# ESPRO_2.net
KiCad netlist of a schematic drawn in EAGLE
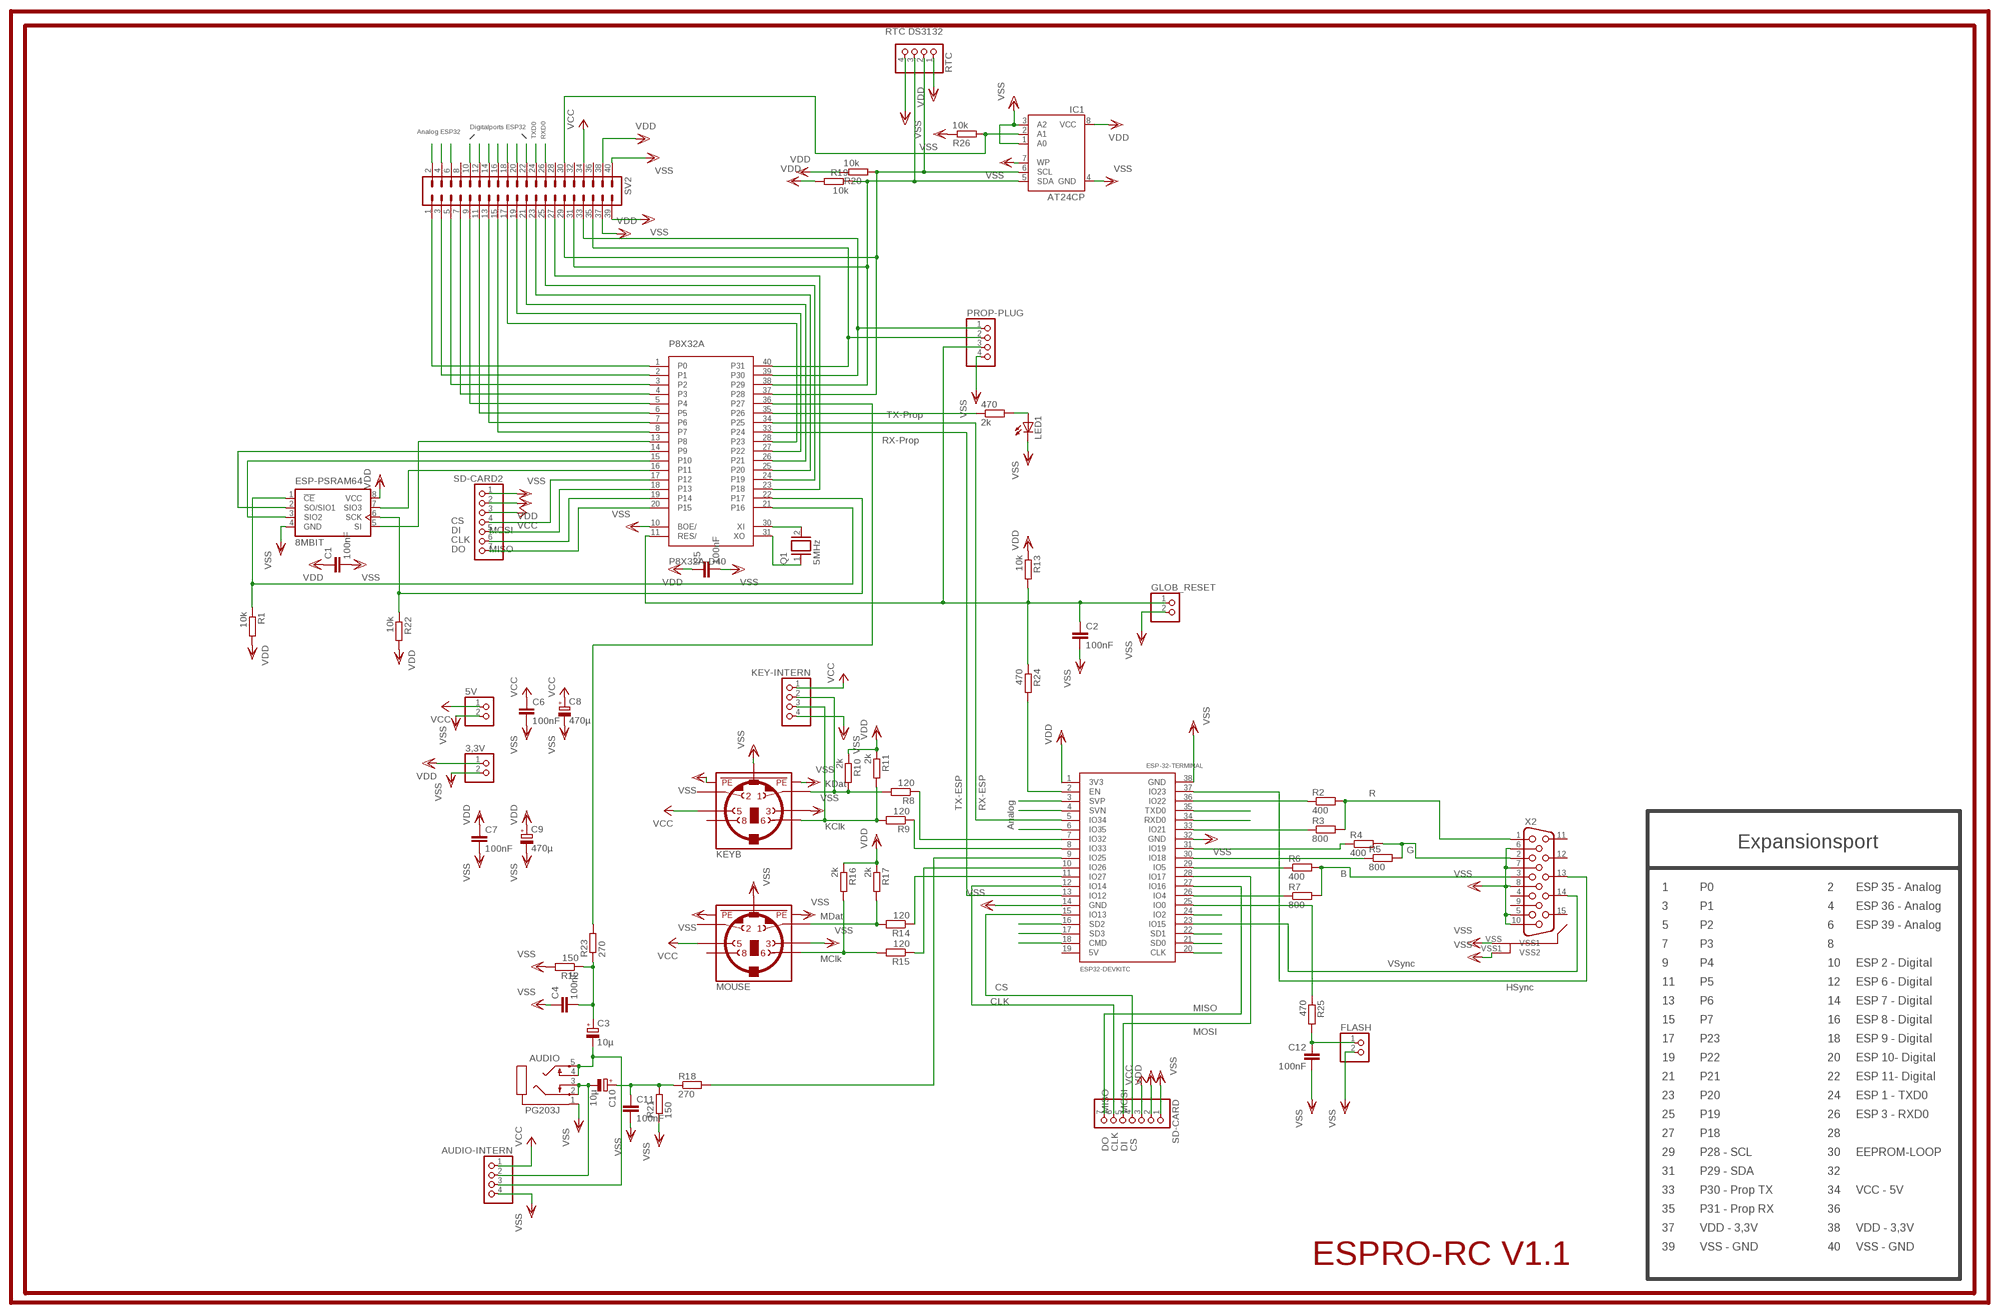
[diagram p0: schematic, sheet 1]

(export (version "E")
  (design (tool "Eeschema 10.0.6"))
  (components
    (comp (ref "3,3V")
      (value "PINHD-1X2")
      (footprint "eagle-import:1X02")
      (libsource (lib "eagle-import") (part "PINHD-1X2"))
    )
    (comp (ref "5V")
      (value "PINHD-1X2")
      (footprint "eagle-import:1X02")
      (libsource (lib "eagle-import") (part "PINHD-1X2"))
    )
    (comp (ref "470")
      (value "2k")
      (footprint "eagle-import:0204_7")
      (libsource (lib "eagle-import") (part "R-EU_0204/7"))
    )
    (comp (ref "AUDIO")
      (value "PG203J")
      (footprint "eagle-import:PG203J")
      (libsource (lib "eagle-import") (part "PG203J"))
    )
    (comp (ref "AUDIO-INTERN")
      (value "PINHD-1X4")
      (footprint "eagle-import:1X04")
      (libsource (lib "eagle-import") (part "PINHD-1X4"))
    )
    (comp (ref "C1")
      (value "100nF")
      (footprint "eagle-import:C025-030X050")
      (libsource (lib "eagle-import") (part "C-EU025-030X050"))
    )
    (comp (ref "C2")
      (value "100nF")
      (footprint "eagle-import:C025-030X050")
      (libsource (lib "eagle-import") (part "C-EU025-030X050"))
    )
    (comp (ref "C3")
      (value "10µ")
      (footprint "eagle-import:E2-4")
      (libsource (lib "eagle-import") (part "CPOL-EUE2-4"))
    )
    (comp (ref "C4")
      (value "100nF")
      (footprint "eagle-import:C025-030X050")
      (libsource (lib "eagle-import") (part "C-EU025-030X050"))
    )
    (comp (ref "C5")
      (value "100nF")
      (footprint "eagle-import:C025-030X050")
      (libsource (lib "eagle-import") (part "C-EU025-030X050"))
    )
    (comp (ref "C6")
      (value "100nF")
      (footprint "eagle-import:C025-030X050")
      (libsource (lib "eagle-import") (part "C-EU025-030X050"))
    )
    (comp (ref "C7")
      (value "100nF")
      (footprint "eagle-import:C025-030X050")
      (libsource (lib "eagle-import") (part "C-EU025-030X050"))
    )
    (comp (ref "C8")
      (value "470µ")
      (footprint "eagle-import:E3,5-10")
      (libsource (lib "eagle-import") (part "CPOL-EUE3.5-10"))
    )
    (comp (ref "C9")
      (value "470µ")
      (footprint "eagle-import:E3,5-10")
      (libsource (lib "eagle-import") (part "CPOL-EUE3.5-10"))
    )
    (comp (ref "C10")
      (value "10µ")
      (footprint "eagle-import:E2-4")
      (libsource (lib "eagle-import") (part "CPOL-EUE2-4"))
    )
    (comp (ref "C11")
      (value "100nF")
      (footprint "eagle-import:C025-030X050")
      (libsource (lib "eagle-import") (part "C-EU025-030X050"))
    )
    (comp (ref "C12")
      (value "100nF")
      (footprint "eagle-import:C025-030X050")
      (libsource (lib "eagle-import") (part "C-EU025-030X050"))
    )
    (comp (ref "ESP-32-TERMINAL")
      (value "ESP32DEVKITC")
      (footprint "eagle-import:ESP32-DEVKITC")
      (libsource (lib "eagle-import") (part "ESP32DEVKITC"))
    )
    (comp (ref "ESP-PSRAM64")
      (value "8MBIT")
      (footprint "eagle-import:DIL08")
      (libsource (lib "eagle-import") (part "AT25P"))
    )
    (comp (ref "FLASH")
      (value "PINHD-1X2")
      (footprint "eagle-import:1X02")
      (libsource (lib "eagle-import") (part "PINHD-1X2"))
    )
    (comp (ref "GLOB_RESET")
      (value "PINHD-1X2")
      (footprint "eagle-import:1X02")
      (libsource (lib "eagle-import") (part "PINHD-1X2"))
    )
    (comp (ref "IC1")
      (value "AT24CP")
      (footprint "eagle-import:DIL08")
      (fields (field (name "MPN") "AT24C1024BW-SH-B"))
      (libsource (lib "eagle-import") (part "AT24CP"))
    )
    (comp (ref "KEY-INTERN")
      (value "PINHD-1X4")
      (footprint "eagle-import:1X04")
      (libsource (lib "eagle-import") (part "PINHD-1X4"))
    )
    (comp (ref "KEYB")
      (value "MINI_DIN_6")
      (footprint "eagle-import:M_DIN6")
      (libsource (lib "eagle-import") (part "MINI_DIN_6"))
    )
    (comp (ref "LED1")
      (value "LED5MM")
      (footprint "eagle-import:LED5MM")
      (libsource (lib "eagle-import") (part "LED5MM"))
    )
    (comp (ref "MOUSE")
      (value "MINI_DIN_6")
      (footprint "eagle-import:M_DIN6")
      (libsource (lib "eagle-import") (part "MINI_DIN_6"))
    )
    (comp (ref "P8X32A")
      (value "P8X32A-D40")
      (footprint "eagle-import:P8X32A-D40")
      (libsource (lib "eagle-import") (part "P8X32A-D40"))
    )
    (comp (ref "PROP-PLUG")
      (value "PINHD-1X4")
      (footprint "eagle-import:1X04")
      (libsource (lib "eagle-import") (part "PINHD-1X4"))
    )
    (comp (ref "Q1")
      (value "5MHz")
      (footprint "eagle-import:QS")
      (libsource (lib "eagle-import") (part "XTAL/S"))
    )
    (comp (ref "R1")
      (value "10k")
      (footprint "eagle-import:0204_7")
      (libsource (lib "eagle-import") (part "R-EU_0204/7"))
    )
    (comp (ref "R2")
      (value "400")
      (footprint "eagle-import:0204_7")
      (libsource (lib "eagle-import") (part "R-EU_0204/7"))
    )
    (comp (ref "R3")
      (value "800")
      (footprint "eagle-import:0204_7")
      (libsource (lib "eagle-import") (part "R-EU_0204/7"))
    )
    (comp (ref "R4")
      (value "400")
      (footprint "eagle-import:0204_7")
      (libsource (lib "eagle-import") (part "R-EU_0204/7"))
    )
    (comp (ref "R5")
      (value "800")
      (footprint "eagle-import:0204_7")
      (libsource (lib "eagle-import") (part "R-EU_0204/7"))
    )
    (comp (ref "R6")
      (value "400")
      (footprint "eagle-import:0204_7")
      (libsource (lib "eagle-import") (part "R-EU_0204/7"))
    )
    (comp (ref "R7")
      (value "800")
      (footprint "eagle-import:0204_7")
      (libsource (lib "eagle-import") (part "R-EU_0204/7"))
    )
    (comp (ref "R8")
      (value "120")
      (footprint "eagle-import:0204_7")
      (libsource (lib "eagle-import") (part "R-EU_0204/7"))
    )
    (comp (ref "R9")
      (value "120")
      (footprint "eagle-import:0204_7")
      (libsource (lib "eagle-import") (part "R-EU_0204/7"))
    )
    (comp (ref "R10")
      (value "2k")
      (footprint "eagle-import:0204_7")
      (libsource (lib "eagle-import") (part "R-EU_0204/7"))
    )
    (comp (ref "R11")
      (value "2k")
      (footprint "eagle-import:0204_7")
      (libsource (lib "eagle-import") (part "R-EU_0204/7"))
    )
    (comp (ref "R12")
      (value "150")
      (footprint "eagle-import:0204_7")
      (libsource (lib "eagle-import") (part "R-EU_0204/7"))
    )
    (comp (ref "R13")
      (value "10k")
      (footprint "eagle-import:0204_7")
      (libsource (lib "eagle-import") (part "R-EU_0204/7"))
    )
    (comp (ref "R14")
      (value "120")
      (footprint "eagle-import:0204_7")
      (libsource (lib "eagle-import") (part "R-EU_0204/7"))
    )
    (comp (ref "R15")
      (value "120")
      (footprint "eagle-import:0204_7")
      (libsource (lib "eagle-import") (part "R-EU_0204/7"))
    )
    (comp (ref "R16")
      (value "2k")
      (footprint "eagle-import:0204_7")
      (libsource (lib "eagle-import") (part "R-EU_0204/7"))
    )
    (comp (ref "R17")
      (value "2k")
      (footprint "eagle-import:0204_7")
      (libsource (lib "eagle-import") (part "R-EU_0204/7"))
    )
    (comp (ref "R18")
      (value "270")
      (footprint "eagle-import:0204_7")
      (libsource (lib "eagle-import") (part "R-EU_0204/7"))
    )
    (comp (ref "R19")
      (value "10k")
      (footprint "eagle-import:0204_7")
      (libsource (lib "eagle-import") (part "R-EU_0204/7"))
    )
    (comp (ref "R20")
      (value "10k")
      (footprint "eagle-import:0204_7")
      (libsource (lib "eagle-import") (part "R-EU_0204/7"))
    )
    (comp (ref "R21")
      (value "150")
      (footprint "eagle-import:0204_7")
      (libsource (lib "eagle-import") (part "R-EU_0204/7"))
    )
    (comp (ref "R22")
      (value "10k")
      (footprint "eagle-import:0204_7")
      (libsource (lib "eagle-import") (part "R-EU_0204/7"))
    )
    (comp (ref "R23")
      (value "270")
      (footprint "eagle-import:0204_7")
      (libsource (lib "eagle-import") (part "R-EU_0204/7"))
    )
    (comp (ref "R24")
      (value "470")
      (footprint "eagle-import:0204_7")
      (libsource (lib "eagle-import") (part "R-EU_0204/7"))
    )
    (comp (ref "R25")
      (value "470")
      (footprint "eagle-import:0204_7")
      (libsource (lib "eagle-import") (part "R-EU_0204/7"))
    )
    (comp (ref "R26")
      (value "10k")
      (footprint "eagle-import:0204_7")
      (libsource (lib "eagle-import") (part "R-EU_0204/7"))
    )
    (comp (ref "RTC")
      (value "PINHD-1X4")
      (footprint "eagle-import:1X04")
      (libsource (lib "eagle-import") (part "PINHD-1X4"))
    )
    (comp (ref "SD-CARD")
      (value "PINHD-1X7")
      (footprint "eagle-import:1X07")
      (libsource (lib "eagle-import") (part "PINHD-1X7"))
    )
    (comp (ref "SD-CARD2")
      (value "PINHD-1X7")
      (footprint "eagle-import:1X07")
      (libsource (lib "eagle-import") (part "PINHD-1X7"))
    )
    (comp (ref "SV2")
      (value "ML40L")
      (footprint "eagle-import:ML40L")
      (libsource (lib "eagle-import") (part "ML40L"))
    )
    (comp (ref "X2")
      (value "HF15H")
      (footprint "eagle-import:HDF15H")
      (libsource (lib "eagle-import") (part "HF15H"))
    )
  )
  (nets
    (net (code "1") (name "/A35") (class "Default")
      (node (ref "ESP-32-TERMINAL") (pin "6") (pinfunction "IO35_6") (pintype "bidirectional"))
      (node (ref "SV2") (pin "2") (pinfunction "2_2") (pintype "passive"))
    )
    (net (code "2") (name "/A36") (class "Default")
      (node (ref "ESP-32-TERMINAL") (pin "3") (pinfunction "SVP_3") (pintype "bidirectional"))
      (node (ref "SV2") (pin "4") (pinfunction "4_4") (pintype "passive"))
    )
    (net (code "3") (name "/A39") (class "Default")
      (node (ref "ESP-32-TERMINAL") (pin "4") (pinfunction "SVN_4") (pintype "bidirectional"))
      (node (ref "SV2") (pin "6") (pinfunction "6_6") (pintype "passive"))
    )
    (net (code "4") (name "/E2") (class "Default")
      (node (ref "ESP-32-TERMINAL") (pin "24") (pinfunction "IO2_24") (pintype "bidirectional"))
      (node (ref "ESP-32-TERMINAL") (pin "5") (pinfunction "IO34_5") (pintype "bidirectional"))
      (node (ref "P8X32A") (pin "34") (pinfunction "P25_34") (pintype "bidirectional"))
      (node (ref "SV2") (pin "10") (pinfunction "10_10") (pintype "passive"))
    )
    (net (code "5") (name "/E6") (class "Default")
      (node (ref "ESP-32-TERMINAL") (pin "20") (pinfunction "CLK_20") (pintype "bidirectional"))
      (node (ref "SV2") (pin "12") (pinfunction "12_12") (pintype "passive"))
    )
    (net (code "6") (name "/E7") (class "Default")
      (node (ref "ESP-32-TERMINAL") (pin "21") (pinfunction "SD0_21") (pintype "bidirectional"))
      (node (ref "SV2") (pin "14") (pinfunction "14_14") (pintype "passive"))
    )
    (net (code "7") (name "/E8") (class "Default")
      (node (ref "ESP-32-TERMINAL") (pin "22") (pinfunction "SD1_22") (pintype "bidirectional"))
      (node (ref "SV2") (pin "16") (pinfunction "16_16") (pintype "passive"))
    )
    (net (code "8") (name "/E9") (class "Default")
      (node (ref "ESP-32-TERMINAL") (pin "16") (pinfunction "SD2_16") (pintype "bidirectional"))
      (node (ref "SV2") (pin "18") (pinfunction "18_18") (pintype "passive"))
    )
    (net (code "9") (name "/E10") (class "Default")
      (node (ref "ESP-32-TERMINAL") (pin "17") (pinfunction "SD3_17") (pintype "bidirectional"))
      (node (ref "SV2") (pin "20") (pinfunction "20_20") (pintype "passive"))
    )
    (net (code "10") (name "/E11") (class "Default")
      (node (ref "ESP-32-TERMINAL") (pin "18") (pinfunction "CMD_18") (pintype "bidirectional"))
      (node (ref "SV2") (pin "22") (pinfunction "22_22") (pintype "passive"))
    )
    (net (code "11") (name "/RXD0") (class "Default")
      (node (ref "ESP-32-TERMINAL") (pin "34") (pinfunction "RXD0_34") (pintype "bidirectional"))
      (node (ref "SV2") (pin "26") (pinfunction "26_26") (pintype "passive"))
    )
    (net (code "12") (name "/TXD0") (class "Default")
      (node (ref "ESP-32-TERMINAL") (pin "35") (pinfunction "TXD0_35") (pintype "bidirectional"))
      (node (ref "SV2") (pin "24") (pinfunction "24_24") (pintype "passive"))
    )
    (net (code "13") (name "Net-(470-Pad2)") (class "Default")
      (node (ref "470") (pin "2") (pinfunction "2_2") (pintype "passive"))
      (node (ref "LED1") (pin "A") (pinfunction "A_A") (pintype "passive"))
    )
    (net (code "14") (name "Net-(AUDIO-INTERN-Pad2)") (class "Default")
      (node (ref "AUDIO") (pin "2") (pinfunction "2_2") (pintype "passive"))
      (node (ref "AUDIO") (pin "3") (pinfunction "3_3") (pintype "passive"))
      (node (ref "AUDIO-INTERN") (pin "2") (pinfunction "2_2") (pintype "passive"))
      (node (ref "C10") (pin "-") (pinfunction "-_-") (pintype "passive"))
    )
    (net (code "15") (name "Net-(AUDIO-INTERN-Pad3)") (class "Default")
      (node (ref "AUDIO") (pin "4") (pinfunction "4_4") (pintype "passive"))
      (node (ref "AUDIO") (pin "5") (pinfunction "5_5") (pintype "passive"))
      (node (ref "AUDIO-INTERN") (pin "3") (pinfunction "3_3") (pintype "passive"))
      (node (ref "C3") (pin "-") (pinfunction "-_-") (pintype "passive"))
    )
    (net (code "16") (name "Net-(C3-Pad+)") (class "Default")
      (node (ref "C3") (pin "+") (pinfunction "+_+") (pintype "passive"))
      (node (ref "C4") (pin "2") (pinfunction "2_2") (pintype "passive"))
      (node (ref "R12") (pin "1") (pinfunction "1_1") (pintype "passive"))
      (node (ref "R23") (pin "1") (pinfunction "1_1") (pintype "passive"))
    )
    (net (code "17") (name "Net-(C10-Pad+)") (class "Default")
      (node (ref "C10") (pin "+") (pinfunction "+_+") (pintype "passive"))
      (node (ref "C11") (pin "1") (pinfunction "1_1") (pintype "passive"))
      (node (ref "R18") (pin "1") (pinfunction "1_1") (pintype "passive"))
      (node (ref "R21") (pin "2") (pinfunction "2_2") (pintype "passive"))
    )
    (net (code "18") (name "Net-(C12-Pad1)") (class "Default")
      (node (ref "C12") (pin "1") (pinfunction "1_1") (pintype "passive"))
      (node (ref "FLASH") (pin "1") (pinfunction "1_1") (pintype "passive"))
      (node (ref "R25") (pin "2") (pinfunction "2_2") (pintype "passive"))
    )
    (net (code "19") (name "Net-(ESP-32-TERMINAL-EN)") (class "Default")
      (node (ref "ESP-32-TERMINAL") (pin "2") (pinfunction "EN_2") (pintype "bidirectional"))
      (node (ref "R24") (pin "2") (pinfunction "2_2") (pintype "passive"))
    )
    (net (code "20") (name "Net-(ESP-32-TERMINAL-IO0)") (class "Default")
      (node (ref "ESP-32-TERMINAL") (pin "25") (pinfunction "IO0_25") (pintype "bidirectional"))
      (node (ref "R25") (pin "1") (pinfunction "1_1") (pintype "passive"))
    )
    (net (code "21") (name "Net-(ESP-32-TERMINAL-IO4)") (class "Default")
      (node (ref "ESP-32-TERMINAL") (pin "26") (pinfunction "IO4_26") (pintype "bidirectional"))
      (node (ref "R7") (pin "1") (pinfunction "1_1") (pintype "passive"))
    )
    (net (code "22") (name "Net-(ESP-32-TERMINAL-IO5)") (class "Default")
      (node (ref "ESP-32-TERMINAL") (pin "29") (pinfunction "IO5_29") (pintype "bidirectional"))
      (node (ref "R6") (pin "1") (pinfunction "1_1") (pintype "passive"))
    )
    (net (code "23") (name "Net-(ESP-32-TERMINAL-IO12)") (class "Default")
      (node (ref "ESP-32-TERMINAL") (pin "13") (pinfunction "IO12_13") (pintype "bidirectional"))
      (node (ref "P8X32A") (pin "33") (pinfunction "P24_33") (pintype "bidirectional"))
    )
    (net (code "24") (name "Net-(ESP-32-TERMINAL-IO13)") (class "Default")
      (node (ref "ESP-32-TERMINAL") (pin "15") (pinfunction "IO13_15") (pintype "bidirectional"))
      (node (ref "SD-CARD") (pin "4") (pinfunction "4_4") (pintype "passive"))
    )
    (net (code "25") (name "Net-(ESP-32-TERMINAL-IO14)") (class "Default")
      (node (ref "ESP-32-TERMINAL") (pin "12") (pinfunction "IO14_12") (pintype "bidirectional"))
      (node (ref "SD-CARD") (pin "6") (pinfunction "6_6") (pintype "passive"))
    )
    (net (code "26") (name "Net-(ESP-32-TERMINAL-IO15)") (class "Default")
      (node (ref "ESP-32-TERMINAL") (pin "23") (pinfunction "IO15_23") (pintype "bidirectional"))
      (node (ref "X2") (pin "14") (pinfunction "14_14") (pintype "passive"))
    )
    (net (code "27") (name "Net-(ESP-32-TERMINAL-IO16)") (class "Default")
      (node (ref "ESP-32-TERMINAL") (pin "27") (pinfunction "IO16_27") (pintype "bidirectional"))
      (node (ref "SD-CARD") (pin "7") (pinfunction "7_7") (pintype "passive"))
    )
    (net (code "28") (name "Net-(ESP-32-TERMINAL-IO17)") (class "Default")
      (node (ref "ESP-32-TERMINAL") (pin "28") (pinfunction "IO17_28") (pintype "bidirectional"))
      (node (ref "SD-CARD") (pin "5") (pinfunction "5_5") (pintype "passive"))
    )
    (net (code "29") (name "Net-(ESP-32-TERMINAL-IO18)") (class "Default")
      (node (ref "ESP-32-TERMINAL") (pin "30") (pinfunction "IO18_30") (pintype "bidirectional"))
      (node (ref "R5") (pin "1") (pinfunction "1_1") (pintype "passive"))
    )
    (net (code "30") (name "Net-(ESP-32-TERMINAL-IO19)") (class "Default")
      (node (ref "ESP-32-TERMINAL") (pin "31") (pinfunction "IO19_31") (pintype "bidirectional"))
      (node (ref "R4") (pin "1") (pinfunction "1_1") (pintype "passive"))
    )
    (net (code "31") (name "Net-(ESP-32-TERMINAL-IO21)") (class "Default")
      (node (ref "ESP-32-TERMINAL") (pin "33") (pinfunction "IO21_33") (pintype "bidirectional"))
      (node (ref "R3") (pin "1") (pinfunction "1_1") (pintype "passive"))
    )
    (net (code "32") (name "Net-(ESP-32-TERMINAL-IO22)") (class "Default")
      (node (ref "ESP-32-TERMINAL") (pin "36") (pinfunction "IO22_36") (pintype "bidirectional"))
      (node (ref "R2") (pin "1") (pinfunction "1_1") (pintype "passive"))
    )
    (net (code "33") (name "Net-(ESP-32-TERMINAL-IO23)") (class "Default")
      (node (ref "ESP-32-TERMINAL") (pin "37") (pinfunction "IO23_37") (pintype "bidirectional"))
      (node (ref "X2") (pin "13") (pinfunction "13_13") (pintype "passive"))
    )
    (net (code "34") (name "Net-(ESP-32-TERMINAL-IO25)") (class "Default")
      (node (ref "ESP-32-TERMINAL") (pin "9") (pinfunction "IO25_9") (pintype "bidirectional"))
      (node (ref "R18") (pin "2") (pinfunction "2_2") (pintype "passive"))
    )
    (net (code "35") (name "Net-(ESP-32-TERMINAL-IO26)") (class "Default")
      (node (ref "ESP-32-TERMINAL") (pin "10") (pinfunction "IO26_10") (pintype "bidirectional"))
      (node (ref "R15") (pin "1") (pinfunction "1_1") (pintype "passive"))
    )
    (net (code "36") (name "Net-(ESP-32-TERMINAL-IO27)") (class "Default")
      (node (ref "ESP-32-TERMINAL") (pin "11") (pinfunction "IO27_11") (pintype "bidirectional"))
      (node (ref "R14") (pin "1") (pinfunction "1_1") (pintype "passive"))
    )
    (net (code "37") (name "Net-(ESP-32-TERMINAL-IO32)") (class "Default")
      (node (ref "ESP-32-TERMINAL") (pin "7") (pinfunction "IO32_7") (pintype "bidirectional"))
      (node (ref "R8") (pin "1") (pinfunction "1_1") (pintype "passive"))
    )
    (net (code "38") (name "Net-(ESP-32-TERMINAL-IO33)") (class "Default")
      (node (ref "ESP-32-TERMINAL") (pin "8") (pinfunction "IO33_8") (pintype "bidirectional"))
      (node (ref "R9") (pin "1") (pinfunction "1_1") (pintype "passive"))
    )
    (net (code "39") (name "Net-(ESP-PSRAM64-SCK)") (class "Default")
      (node (ref "ESP-PSRAM64") (pin "6") (pinfunction "SCK_6") (pintype "input"))
      (node (ref "P8X32A") (pin "22") (pinfunction "P17_22") (pintype "bidirectional"))
      (node (ref "R22") (pin "1") (pinfunction "1_1") (pintype "passive"))
    )
    (net (code "40") (name "Net-(ESP-PSRAM64-SI)") (class "Default")
      (node (ref "ESP-PSRAM64") (pin "5") (pinfunction "SI_5") (pintype "input"))
      (node (ref "P8X32A") (pin "13") (pinfunction "P8_13") (pintype "bidirectional"))
    )
    (net (code "41") (name "Net-(ESP-PSRAM64-SIO2)") (class "Default")
      (node (ref "ESP-PSRAM64") (pin "3") (pinfunction "SIO2_3") (pintype "input"))
      (node (ref "P8X32A") (pin "15") (pinfunction "P10_15") (pintype "bidirectional"))
    )
    (net (code "42") (name "Net-(ESP-PSRAM64-SIO3)") (class "Default")
      (node (ref "ESP-PSRAM64") (pin "7") (pinfunction "SIO3_7") (pintype "input"))
      (node (ref "P8X32A") (pin "16") (pinfunction "P11_16") (pintype "bidirectional"))
    )
    (net (code "43") (name "Net-(ESP-PSRAM64-SO{slash}SIO1)") (class "Default")
      (node (ref "ESP-PSRAM64") (pin "2") (pinfunction "SO/SIO1_2") (pintype "output"))
      (node (ref "P8X32A") (pin "14") (pinfunction "P9_14") (pintype "bidirectional"))
    )
    (net (code "44") (name "Net-(ESP-PSRAM64-~{CE})") (class "Default")
      (node (ref "ESP-PSRAM64") (pin "1") (pinfunction "~{CE}_1") (pintype "input"))
      (node (ref "P8X32A") (pin "21") (pinfunction "P16_21") (pintype "bidirectional"))
      (node (ref "R1") (pin "1") (pinfunction "1_1") (pintype "passive"))
    )
    (net (code "45") (name "Net-(IC1-A1)") (class "Default")
      (node (ref "IC1") (pin "2") (pinfunction "A1_2") (pintype "input"))
      (node (ref "R26") (pin "2") (pinfunction "2_2") (pintype "passive"))
      (node (ref "SV2") (pin "30") (pinfunction "30_30") (pintype "passive"))
    )
    (net (code "46") (name "Net-(IC1-SCL)") (class "Default")
      (node (ref "IC1") (pin "6") (pinfunction "SCL_6") (pintype "bidirectional"))
      (node (ref "P8X32A") (pin "37") (pinfunction "P28_37") (pintype "bidirectional"))
      (node (ref "R20") (pin "2") (pinfunction "2_2") (pintype "passive"))
      (node (ref "RTC") (pin "2") (pinfunction "2_2") (pintype "passive"))
      (node (ref "SV2") (pin "29") (pinfunction "29_29") (pintype "passive"))
    )
    (net (code "47") (name "Net-(IC1-SDA)") (class "Default")
      (node (ref "IC1") (pin "5") (pinfunction "SDA_5") (pintype "bidirectional"))
      (node (ref "P8X32A") (pin "38") (pinfunction "P29_38") (pintype "bidirectional"))
      (node (ref "R19") (pin "1") (pinfunction "1_1") (pintype "passive"))
      (node (ref "RTC") (pin "3") (pinfunction "3_3") (pintype "passive"))
      (node (ref "SV2") (pin "31") (pinfunction "31_31") (pintype "passive"))
    )
    (net (code "48") (name "Net-(KEY-INTERN-Pad2)") (class "Default")
      (node (ref "KEY-INTERN") (pin "2") (pinfunction "2_2") (pintype "passive"))
      (node (ref "KEYB") (pin "1") (pinfunction "1_1") (pintype "passive"))
      (node (ref "R10") (pin "2") (pinfunction "2_2") (pintype "passive"))
      (node (ref "R8") (pin "2") (pinfunction "2_2") (pintype "passive"))
    )
    (net (code "49") (name "Net-(KEY-INTERN-Pad3)") (class "Default")
      (node (ref "KEY-INTERN") (pin "3") (pinfunction "3_3") (pintype "passive"))
      (node (ref "KEYB") (pin "6") (pinfunction "6_6") (pintype "passive"))
      (node (ref "R11") (pin "2") (pinfunction "2_2") (pintype "passive"))
      (node (ref "R9") (pin "2") (pinfunction "2_2") (pintype "passive"))
    )
    (net (code "50") (name "Net-(MOUSE-Pad1)") (class "Default")
      (node (ref "MOUSE") (pin "1") (pinfunction "1_1") (pintype "passive"))
      (node (ref "R14") (pin "2") (pinfunction "2_2") (pintype "passive"))
      (node (ref "R17") (pin "2") (pinfunction "2_2") (pintype "passive"))
    )
    (net (code "51") (name "Net-(MOUSE-Pad6)") (class "Default")
      (node (ref "MOUSE") (pin "6") (pinfunction "6_6") (pintype "passive"))
      (node (ref "R15") (pin "2") (pinfunction "2_2") (pintype "passive"))
      (node (ref "R16") (pin "2") (pinfunction "2_2") (pintype "passive"))
    )
    (net (code "52") (name "Net-(P8X32AB-P0)") (class "Default")
      (node (ref "P8X32A") (pin "1") (pinfunction "P0_1") (pintype "bidirectional"))
      (node (ref "SV2") (pin "1") (pinfunction "1_1") (pintype "passive"))
    )
    (net (code "53") (name "Net-(P8X32AB-P1)") (class "Default")
      (node (ref "P8X32A") (pin "2") (pinfunction "P1_2") (pintype "bidirectional"))
      (node (ref "SV2") (pin "3") (pinfunction "3_3") (pintype "passive"))
    )
    (net (code "54") (name "Net-(P8X32AB-P2)") (class "Default")
      (node (ref "P8X32A") (pin "3") (pinfunction "P2_3") (pintype "bidirectional"))
      (node (ref "SV2") (pin "5") (pinfunction "5_5") (pintype "passive"))
    )
    (net (code "55") (name "Net-(P8X32AB-P3)") (class "Default")
      (node (ref "P8X32A") (pin "4") (pinfunction "P3_4") (pintype "bidirectional"))
      (node (ref "SV2") (pin "7") (pinfunction "7_7") (pintype "passive"))
    )
    (net (code "56") (name "Net-(P8X32AB-P4)") (class "Default")
      (node (ref "P8X32A") (pin "5") (pinfunction "P4_5") (pintype "bidirectional"))
      (node (ref "SV2") (pin "9") (pinfunction "9_9") (pintype "passive"))
    )
    (net (code "57") (name "Net-(P8X32AB-P5)") (class "Default")
      (node (ref "P8X32A") (pin "6") (pinfunction "P5_6") (pintype "bidirectional"))
      (node (ref "SV2") (pin "11") (pinfunction "11_11") (pintype "passive"))
    )
    (net (code "58") (name "Net-(P8X32AB-P6)") (class "Default")
      (node (ref "P8X32A") (pin "7") (pinfunction "P6_7") (pintype "bidirectional"))
      (node (ref "SV2") (pin "13") (pinfunction "13_13") (pintype "passive"))
    )
    (net (code "59") (name "Net-(P8X32AB-P7)") (class "Default")
      (node (ref "P8X32A") (pin "8") (pinfunction "P7_8") (pintype "bidirectional"))
      (node (ref "SV2") (pin "15") (pinfunction "15_15") (pintype "passive"))
    )
    (net (code "60") (name "Net-(P8X32AB-P12)") (class "Default")
      (node (ref "P8X32A") (pin "17") (pinfunction "P12_17") (pintype "bidirectional"))
      (node (ref "SD-CARD2") (pin "4") (pinfunction "4_4") (pintype "passive"))
    )
    (net (code "61") (name "Net-(P8X32AB-P13)") (class "Default")
      (node (ref "P8X32A") (pin "18") (pinfunction "P13_18") (pintype "bidirectional"))
      (node (ref "SD-CARD2") (pin "5") (pinfunction "5_5") (pintype "passive"))
    )
    (net (code "62") (name "Net-(P8X32AB-P14)") (class "Default")
      (node (ref "P8X32A") (pin "19") (pinfunction "P14_19") (pintype "bidirectional"))
      (node (ref "SD-CARD2") (pin "6") (pinfunction "6_6") (pintype "passive"))
    )
    (net (code "63") (name "Net-(P8X32AB-P15)") (class "Default")
      (node (ref "P8X32A") (pin "20") (pinfunction "P15_20") (pintype "bidirectional"))
      (node (ref "SD-CARD2") (pin "7") (pinfunction "7_7") (pintype "passive"))
    )
    (net (code "64") (name "Net-(P8X32AB-P18)") (class "Default")
      (node (ref "P8X32A") (pin "23") (pinfunction "P18_23") (pintype "bidirectional"))
      (node (ref "SV2") (pin "27") (pinfunction "27_27") (pintype "passive"))
    )
    (net (code "65") (name "Net-(P8X32AB-P19)") (class "Default")
      (node (ref "P8X32A") (pin "24") (pinfunction "P19_24") (pintype "bidirectional"))
      (node (ref "SV2") (pin "25") (pinfunction "25_25") (pintype "passive"))
    )
    (net (code "66") (name "Net-(P8X32AB-P20)") (class "Default")
      (node (ref "P8X32A") (pin "25") (pinfunction "P20_25") (pintype "bidirectional"))
      (node (ref "SV2") (pin "23") (pinfunction "23_23") (pintype "passive"))
    )
    (net (code "67") (name "Net-(P8X32AB-P21)") (class "Default")
      (node (ref "P8X32A") (pin "26") (pinfunction "P21_26") (pintype "bidirectional"))
      (node (ref "SV2") (pin "21") (pinfunction "21_21") (pintype "passive"))
    )
    (net (code "68") (name "Net-(P8X32AB-P22)") (class "Default")
      (node (ref "P8X32A") (pin "27") (pinfunction "P22_27") (pintype "bidirectional"))
      (node (ref "SV2") (pin "19") (pinfunction "19_19") (pintype "passive"))
    )
    (net (code "69") (name "Net-(P8X32AB-P23)") (class "Default")
      (node (ref "P8X32A") (pin "28") (pinfunction "P23_28") (pintype "bidirectional"))
      (node (ref "SV2") (pin "17") (pinfunction "17_17") (pintype "passive"))
    )
    (net (code "70") (name "Net-(P8X32AB-P26)") (class "Default")
      (node (ref "470") (pin "1") (pinfunction "1_1") (pintype "passive"))
      (node (ref "P8X32A") (pin "35") (pinfunction "P26_35") (pintype "bidirectional"))
    )
    (net (code "71") (name "Net-(P8X32AB-P27)") (class "Default")
      (node (ref "P8X32A") (pin "36") (pinfunction "P27_36") (pintype "bidirectional"))
      (node (ref "R23") (pin "2") (pinfunction "2_2") (pintype "passive"))
    )
    (net (code "72") (name "Net-(P8X32AB-P30)") (class "Default")
      (node (ref "P8X32A") (pin "39") (pinfunction "P30_39") (pintype "bidirectional"))
      (node (ref "PROP-PLUG") (pin "1") (pinfunction "1_1") (pintype "passive"))
      (node (ref "SV2") (pin "33") (pinfunction "33_33") (pintype "passive"))
    )
    (net (code "73") (name "Net-(P8X32AB-P31)") (class "Default")
      (node (ref "P8X32A") (pin "40") (pinfunction "P31_40") (pintype "bidirectional"))
      (node (ref "PROP-PLUG") (pin "2") (pinfunction "2_2") (pintype "passive"))
      (node (ref "SV2") (pin "35") (pinfunction "35_35") (pintype "passive"))
    )
    (net (code "74") (name "Net-(P8X32AB-RES{slash})") (class "Default")
      (node (ref "C2") (pin "1") (pinfunction "1_1") (pintype "passive"))
      (node (ref "GLOB_RESET") (pin "1") (pinfunction "1_1") (pintype "passive"))
      (node (ref "P8X32A") (pin "11") (pinfunction "RES/_11") (pintype "bidirectional"))
      (node (ref "PROP-PLUG") (pin "3") (pinfunction "3_3") (pintype "passive"))
      (node (ref "R13") (pin "2") (pinfunction "2_2") (pintype "passive"))
      (node (ref "R24") (pin "1") (pinfunction "1_1") (pintype "passive"))
    )
    (net (code "75") (name "Net-(P8X32AB-XI)") (class "Default")
      (node (ref "P8X32A") (pin "30") (pinfunction "XI_30") (pintype "input"))
      (node (ref "Q1") (pin "2") (pinfunction "2_2") (pintype "passive"))
    )
    (net (code "76") (name "Net-(P8X32AB-XO)") (class "Default")
      (node (ref "P8X32A") (pin "31") (pinfunction "XO_31") (pintype "output"))
      (node (ref "Q1") (pin "1") (pinfunction "1_1") (pintype "passive"))
    )
    (net (code "77") (name "Net-(R2-Pad2)") (class "Default")
      (node (ref "R2") (pin "2") (pinfunction "2_2") (pintype "passive"))
      (node (ref "R3") (pin "2") (pinfunction "2_2") (pintype "passive"))
      (node (ref "X2") (pin "1") (pinfunction "1_1") (pintype "passive"))
    )
    (net (code "78") (name "Net-(R4-Pad2)") (class "Default")
      (node (ref "R4") (pin "2") (pinfunction "2_2") (pintype "passive"))
      (node (ref "R5") (pin "2") (pinfunction "2_2") (pintype "passive"))
      (node (ref "X2") (pin "2") (pinfunction "2_2") (pintype "passive"))
    )
    (net (code "79") (name "Net-(R6-Pad2)") (class "Default")
      (node (ref "R6") (pin "2") (pinfunction "2_2") (pintype "passive"))
      (node (ref "R7") (pin "2") (pinfunction "2_2") (pintype "passive"))
      (node (ref "X2") (pin "3") (pinfunction "3_3") (pintype "passive"))
    )
    (net (code "80") (name "VCC") (class "Default")
      (node (ref "5V") (pin "1") (pinfunction "1_1") (pintype "passive"))
      (node (ref "AUDIO-INTERN") (pin "1") (pinfunction "1_1") (pintype "passive"))
      (node (ref "C6") (pin "1") (pinfunction "1_1") (pintype "passive"))
      (node (ref "C8") (pin "+") (pinfunction "+_+") (pintype "passive"))
      (node (ref "KEY-INTERN") (pin "1") (pinfunction "1_1") (pintype "passive"))
      (node (ref "KEYB") (pin "5") (pinfunction "5_5") (pintype "passive"))
      (node (ref "MOUSE") (pin "5") (pinfunction "5_5") (pintype "passive"))
      (node (ref "SD-CARD") (pin "3") (pinfunction "3_3") (pintype "passive"))
      (node (ref "SD-CARD2") (pin "3") (pinfunction "3_3") (pintype "passive"))
      (node (ref "SV2") (pin "34") (pinfunction "34_34") (pintype "passive"))
    )
    (net (code "81") (name "VDD") (class "Default")
      (node (ref "3,3V") (pin "1") (pinfunction "1_1") (pintype "passive"))
      (node (ref "C1") (pin "1") (pinfunction "1_1") (pintype "passive"))
      (node (ref "C5") (pin "1") (pinfunction "1_1") (pintype "passive"))
      (node (ref "C7") (pin "1") (pinfunction "1_1") (pintype "passive"))
      (node (ref "C9") (pin "+") (pinfunction "+_+") (pintype "passive"))
      (node (ref "ESP-32-TERMINAL") (pin "1") (pinfunction "3V3_1") (pintype "bidirectional"))
      (node (ref "ESP-PSRAM64") (pin "8") (pinfunction "VCC_8") (pintype "power_in"))
      (node (ref "IC1") (pin "8") (pinfunction "VCC_8") (pintype "power_in"))
      (node (ref "R1") (pin "2") (pinfunction "2_2") (pintype "passive"))
      (node (ref "R10") (pin "1") (pinfunction "1_1") (pintype "passive"))
      (node (ref "R11") (pin "1") (pinfunction "1_1") (pintype "passive"))
      (node (ref "R13") (pin "1") (pinfunction "1_1") (pintype "passive"))
      (node (ref "R16") (pin "1") (pinfunction "1_1") (pintype "passive"))
      (node (ref "R17") (pin "1") (pinfunction "1_1") (pintype "passive"))
      (node (ref "R19") (pin "2") (pinfunction "2_2") (pintype "passive"))
      (node (ref "R20") (pin "1") (pinfunction "1_1") (pintype "passive"))
      (node (ref "R22") (pin "2") (pinfunction "2_2") (pintype "passive"))
      (node (ref "RTC") (pin "1") (pinfunction "1_1") (pintype "passive"))
      (node (ref "SD-CARD") (pin "2") (pinfunction "2_2") (pintype "passive"))
      (node (ref "SD-CARD2") (pin "2") (pinfunction "2_2") (pintype "passive"))
      (node (ref "SV2") (pin "37") (pinfunction "37_37") (pintype "passive"))
      (node (ref "SV2") (pin "38") (pinfunction "38_38") (pintype "passive"))
    )
    (net (code "82") (name "VSS") (class "Default")
      (node (ref "3,3V") (pin "2") (pinfunction "2_2") (pintype "passive"))
      (node (ref "5V") (pin "2") (pinfunction "2_2") (pintype "passive"))
      (node (ref "AUDIO") (pin "1") (pinfunction "1_1") (pintype "passive"))
      (node (ref "AUDIO-INTERN") (pin "4") (pinfunction "4_4") (pintype "passive"))
      (node (ref "C1") (pin "2") (pinfunction "2_2") (pintype "passive"))
      (node (ref "C11") (pin "2") (pinfunction "2_2") (pintype "passive"))
      (node (ref "C12") (pin "2") (pinfunction "2_2") (pintype "passive"))
      (node (ref "C2") (pin "2") (pinfunction "2_2") (pintype "passive"))
      (node (ref "C4") (pin "1") (pinfunction "1_1") (pintype "passive"))
      (node (ref "C5") (pin "2") (pinfunction "2_2") (pintype "passive"))
      (node (ref "C6") (pin "2") (pinfunction "2_2") (pintype "passive"))
      (node (ref "C7") (pin "2") (pinfunction "2_2") (pintype "passive"))
      (node (ref "C8") (pin "-") (pinfunction "-_-") (pintype "passive"))
      (node (ref "C9") (pin "-") (pinfunction "-_-") (pintype "passive"))
      (node (ref "ESP-32-TERMINAL") (pin "14") (pinfunction "GND_14") (pintype "bidirectional"))
      (node (ref "ESP-32-TERMINAL") (pin "32") (pinfunction "GND_32") (pintype "bidirectional"))
      (node (ref "ESP-32-TERMINAL") (pin "38") (pinfunction "GND_38") (pintype "bidirectional"))
      (node (ref "ESP-PSRAM64") (pin "4") (pinfunction "GND_4") (pintype "power_in"))
      (node (ref "FLASH") (pin "2") (pinfunction "2_2") (pintype "passive"))
      (node (ref "GLOB_RESET") (pin "2") (pinfunction "2_2") (pintype "passive"))
      (node (ref "IC1") (pin "1") (pinfunction "A0_1") (pintype "input"))
      (node (ref "IC1") (pin "3") (pinfunction "A2_3") (pintype "input"))
      (node (ref "IC1") (pin "4") (pinfunction "GND_4") (pintype "power_in"))
      (node (ref "IC1") (pin "7") (pinfunction "WP_7") (pintype "input"))
      (node (ref "KEY-INTERN") (pin "4") (pinfunction "4_4") (pintype "passive"))
      (node (ref "KEYB") (pin "3") (pinfunction "3_3") (pintype "passive"))
      (node (ref "KEYB") (pin "SH1") (pinfunction "PE1_SH1") (pintype "power_in"))
      (node (ref "KEYB") (pin "SH2") (pinfunction "PE2_SH2") (pintype "power_in"))
      (node (ref "KEYB") (pin "SH3") (pinfunction "PE3_SH3") (pintype "power_in"))
      (node (ref "LED1") (pin "K") (pinfunction "C_K") (pintype "passive"))
      (node (ref "MOUSE") (pin "3") (pinfunction "3_3") (pintype "passive"))
      (node (ref "MOUSE") (pin "SH1") (pinfunction "PE1_SH1") (pintype "power_in"))
      (node (ref "MOUSE") (pin "SH2") (pinfunction "PE2_SH2") (pintype "power_in"))
      (node (ref "MOUSE") (pin "SH3") (pinfunction "PE3_SH3") (pintype "power_in"))
      (node (ref "P8X32A") (pin "10") (pinfunction "BOE/_10") (pintype "input"))
      (node (ref "PROP-PLUG") (pin "4") (pinfunction "4_4") (pintype "passive"))
      (node (ref "R12") (pin "2") (pinfunction "2_2") (pintype "passive"))
      (node (ref "R21") (pin "1") (pinfunction "1_1") (pintype "passive"))
      (node (ref "R26") (pin "1") (pinfunction "1_1") (pintype "passive"))
      (node (ref "RTC") (pin "4") (pinfunction "4_4") (pintype "passive"))
      (node (ref "SD-CARD") (pin "1") (pinfunction "1_1") (pintype "passive"))
      (node (ref "SD-CARD2") (pin "1") (pinfunction "1_1") (pintype "passive"))
      (node (ref "SV2") (pin "39") (pinfunction "39_39") (pintype "passive"))
      (node (ref "SV2") (pin "40") (pinfunction "40_40") (pintype "passive"))
      (node (ref "X2") (pin "10") (pinfunction "10_10") (pintype "passive"))
      (node (ref "X2") (pin "5") (pinfunction "5_5") (pintype "passive"))
      (node (ref "X2") (pin "6") (pinfunction "6_6") (pintype "passive"))
      (node (ref "X2") (pin "7") (pinfunction "7_7") (pintype "passive"))
      (node (ref "X2") (pin "8") (pinfunction "8_8") (pintype "passive"))
      (node (ref "X2") (pin "VSS") (pinfunction "VSS1_VSS") (pintype "passive"))
      (node (ref "X2") (pin "VSS1") (pinfunction "VSS2_VSS1") (pintype "passive"))
    )
    (net (code "83") (name "unconnected-(ESP-32-TERMINAL-5V-Pad19)") (class "Default")
      (node (ref "ESP-32-TERMINAL") (pin "19") (pinfunction "5V_19") (pintype "bidirectional"))
    )
    (net (code "84") (name "unconnected-(KEYB-Pad2)") (class "Default")
      (node (ref "KEYB") (pin "2") (pinfunction "2_2") (pintype "passive"))
    )
    (net (code "85") (name "unconnected-(KEYB-Pad8)") (class "Default")
      (node (ref "KEYB") (pin "8") (pinfunction "8_8") (pintype "passive"))
    )
    (net (code "86") (name "unconnected-(MOUSE-Pad2)") (class "Default")
      (node (ref "MOUSE") (pin "2") (pinfunction "2_2") (pintype "passive"))
    )
    (net (code "87") (name "unconnected-(MOUSE-Pad8)") (class "Default")
      (node (ref "MOUSE") (pin "8") (pinfunction "8_8") (pintype "passive"))
    )
    (net (code "88") (name "unconnected-(SV2-Pad8)") (class "Default")
      (node (ref "SV2") (pin "8") (pinfunction "8_8") (pintype "passive"))
    )
    (net (code "89") (name "unconnected-(SV2-Pad28)") (class "Default")
      (node (ref "SV2") (pin "28") (pinfunction "28_28") (pintype "passive"))
    )
    (net (code "90") (name "unconnected-(SV2-Pad32)") (class "Default")
      (node (ref "SV2") (pin "32") (pinfunction "32_32") (pintype "passive"))
    )
    (net (code "91") (name "unconnected-(SV2-Pad36)") (class "Default")
      (node (ref "SV2") (pin "36") (pinfunction "36_36") (pintype "passive"))
    )
    (net (code "92") (name "unconnected-(X2-Pad4)") (class "Default")
      (node (ref "X2") (pin "4") (pinfunction "4_4") (pintype "passive"))
    )
    (net (code "93") (name "unconnected-(X2-Pad9)") (class "Default")
      (node (ref "X2") (pin "9") (pinfunction "9_9") (pintype "passive"))
    )
    (net (code "94") (name "unconnected-(X2-Pad11)") (class "Default")
      (node (ref "X2") (pin "11") (pinfunction "11_11") (pintype "passive"))
    )
    (net (code "95") (name "unconnected-(X2-Pad12)") (class "Default")
      (node (ref "X2") (pin "12") (pinfunction "12_12") (pintype "passive"))
    )
    (net (code "96") (name "unconnected-(X2-Pad15)") (class "Default")
      (node (ref "X2") (pin "15") (pinfunction "15_15") (pintype "passive"))
    )
  )
)
